# harjapiirilevy.net
KiCad netlist of a schematic drawn in EAGLE
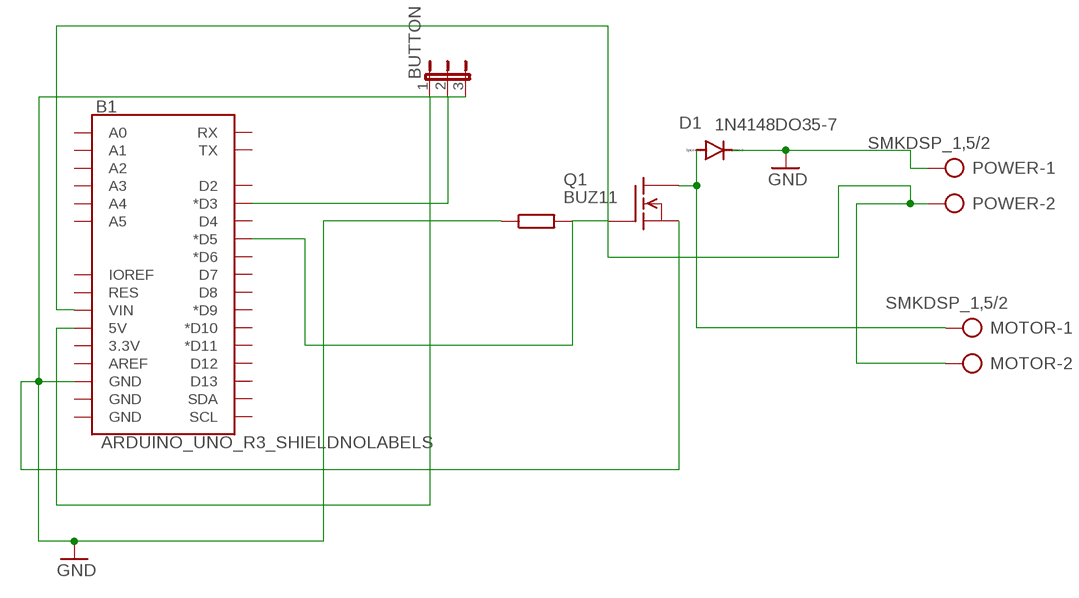
[diagram p0: schematic, sheet 1]

(export (version "E")
  (design (tool "Eeschema 10.0.6"))
  (components
    (comp (ref "B1")
      (value "ARDUINO_UNO_R3_SHIELDNOLABELS")
      (footprint "eagle-import:UNO_R3_SHIELD_NOLABELS")
      (libsource (lib "eagle-import") (part "ARDUINO_UNO_R3_SHIELDNOLABELS"))
    )
    (comp (ref "BUTTON")
      (value "JP2E")
      (footprint "eagle-import:JP2")
      (libsource (lib "eagle-import") (part "JP2E"))
    )
    (comp (ref "D1")
      (value "1N4148DO35-7")
      (footprint "eagle-import:DO35-7")
      (libsource (lib "eagle-import") (part "1N4148DO35-7"))
    )
    (comp (ref "MOTOR")
      (value "SMKDSP_1,5/2")
      (footprint "eagle-import:SMKDSP_1,5_2")
      (fields (field (name "MF") "FARNELL") (field (name "MPN") "1733570"))
      (libsource (lib "eagle-import") (part "SMKDSP_1,5/2"))
    )
    (comp (ref "POWER")
      (value "SMKDSP_1,5/2")
      (footprint "eagle-import:SMKDSP_1,5_2")
      (fields (field (name "MF") "FARNELL") (field (name "MPN") "1733570"))
      (libsource (lib "eagle-import") (part "SMKDSP_1,5/2"))
    )
    (comp (ref "Q1")
      (value "BUZ11")
      (footprint "eagle-import:TO220")
      (libsource (lib "eagle-import") (part "BUZ11"))
    )
  )
  (nets
    (net (code "1") (name "GND") (class "Default")
      (node (ref "B1") (pin "GND@2") (pinfunction "GND_GND@2") (pintype "bidirectional"))
      (node (ref "BUTTON") (pin "3") (pinfunction "3_3") (pintype "passive"))
      (node (ref "D1") (pin "C") (pinfunction "C_C") (pintype "passive"))
      (node (ref "POWER") (pin "1") (pinfunction "KL_1") (pintype "passive"))
      (node (ref "Q1") (pin "3") (pinfunction "S_3") (pintype "passive"))
    )
    (net (code "2") (name "Net-(B1-*D3)") (class "Default")
      (node (ref "B1") (pin "D3") (pinfunction "*D3_D3") (pintype "bidirectional"))
      (node (ref "BUTTON") (pin "2") (pinfunction "2_2") (pintype "passive"))
    )
    (net (code "3") (name "Net-(B1-*D5)") (class "Default")
      (node (ref "B1") (pin "D5") (pinfunction "*D5_D5") (pintype "bidirectional"))
      (node (ref "Q1") (pin "1") (pinfunction "G_1") (pintype "passive"))
    )
    (net (code "4") (name "Net-(B1-Pad5V)") (class "Default")
      (node (ref "B1") (pin "5V") (pinfunction "5V_5V") (pintype "bidirectional"))
      (node (ref "BUTTON") (pin "1") (pinfunction "1_1") (pintype "passive"))
    )
    (net (code "5") (name "Net-(MOTORA-KL)") (class "Default")
      (node (ref "D1") (pin "A") (pinfunction "A_A") (pintype "passive"))
      (node (ref "MOTOR") (pin "1") (pinfunction "KL_1") (pintype "passive"))
      (node (ref "Q1") (pin "2") (pinfunction "D_2") (pintype "passive"))
    )
    (net (code "6") (name "Net-(MOTORB-KL)") (class "Default")
      (node (ref "B1") (pin "VIN") (pinfunction "VIN_VIN") (pintype "bidirectional"))
      (node (ref "MOTOR") (pin "2") (pinfunction "KL_2") (pintype "passive"))
      (node (ref "POWER") (pin "2") (pinfunction "KL_2") (pintype "passive"))
    )
    (net (code "7") (name "unconnected-(B1-*D6-PadD6)") (class "Default")
      (node (ref "B1") (pin "D6") (pinfunction "*D6_D6") (pintype "bidirectional"))
    )
    (net (code "8") (name "unconnected-(B1-*D9-PadD9)") (class "Default")
      (node (ref "B1") (pin "D9") (pinfunction "*D9_D9") (pintype "bidirectional"))
    )
    (net (code "9") (name "unconnected-(B1-*D10-PadD10)") (class "Default")
      (node (ref "B1") (pin "D10") (pinfunction "*D10_D10") (pintype "bidirectional"))
    )
    (net (code "10") (name "unconnected-(B1-*D11-PadD11)") (class "Default")
      (node (ref "B1") (pin "D11") (pinfunction "*D11_D11") (pintype "bidirectional"))
    )
    (net (code "11") (name "unconnected-(B1-GND-PadGND@0)") (class "Default")
      (node (ref "B1") (pin "GND@0") (pinfunction "GND_GND@0") (pintype "bidirectional"))
    )
    (net (code "12") (name "unconnected-(B1-GND-PadGND@1)") (class "Default")
      (node (ref "B1") (pin "GND@1") (pinfunction "GND_GND@1") (pintype "bidirectional"))
    )
    (net (code "13") (name "unconnected-(B1-Pad3.3V)") (class "Default")
      (node (ref "B1") (pin "3.3V") (pinfunction "3.3V_3.3V") (pintype "bidirectional"))
    )
    (net (code "14") (name "unconnected-(B1-PadA0)") (class "Default")
      (node (ref "B1") (pin "A0") (pinfunction "A0_A0") (pintype "bidirectional"))
    )
    (net (code "15") (name "unconnected-(B1-PadA1)") (class "Default")
      (node (ref "B1") (pin "A1") (pinfunction "A1_A1") (pintype "bidirectional"))
    )
    (net (code "16") (name "unconnected-(B1-PadA2)") (class "Default")
      (node (ref "B1") (pin "A2") (pinfunction "A2_A2") (pintype "bidirectional"))
    )
    (net (code "17") (name "unconnected-(B1-PadA3)") (class "Default")
      (node (ref "B1") (pin "A3") (pinfunction "A3_A3") (pintype "bidirectional"))
    )
    (net (code "18") (name "unconnected-(B1-PadA4)") (class "Default")
      (node (ref "B1") (pin "A4") (pinfunction "A4_A4") (pintype "bidirectional"))
    )
    (net (code "19") (name "unconnected-(B1-PadA5)") (class "Default")
      (node (ref "B1") (pin "A5") (pinfunction "A5_A5") (pintype "bidirectional"))
    )
    (net (code "20") (name "unconnected-(B1-PadAREF)") (class "Default")
      (node (ref "B1") (pin "AREF") (pinfunction "AREF_AREF") (pintype "bidirectional"))
    )
    (net (code "21") (name "unconnected-(B1-PadD2)") (class "Default")
      (node (ref "B1") (pin "D2") (pinfunction "D2_D2") (pintype "bidirectional"))
    )
    (net (code "22") (name "unconnected-(B1-PadD4)") (class "Default")
      (node (ref "B1") (pin "D4") (pinfunction "D4_D4") (pintype "bidirectional"))
    )
    (net (code "23") (name "unconnected-(B1-PadD7)") (class "Default")
      (node (ref "B1") (pin "D7") (pinfunction "D7_D7") (pintype "bidirectional"))
    )
    (net (code "24") (name "unconnected-(B1-PadD8)") (class "Default")
      (node (ref "B1") (pin "D8") (pinfunction "D8_D8") (pintype "bidirectional"))
    )
    (net (code "25") (name "unconnected-(B1-PadD12)") (class "Default")
      (node (ref "B1") (pin "D12") (pinfunction "D12_D12") (pintype "bidirectional"))
    )
    (net (code "26") (name "unconnected-(B1-PadD13)") (class "Default")
      (node (ref "B1") (pin "D13") (pinfunction "D13_D13") (pintype "bidirectional"))
    )
    (net (code "27") (name "unconnected-(B1-PadIOREF)") (class "Default")
      (node (ref "B1") (pin "IOREF") (pinfunction "IOREF_IOREF") (pintype "bidirectional"))
    )
    (net (code "28") (name "unconnected-(B1-PadRES)") (class "Default")
      (node (ref "B1") (pin "RES") (pinfunction "RES_RES") (pintype "bidirectional"))
    )
    (net (code "29") (name "unconnected-(B1-PadRX)") (class "Default")
      (node (ref "B1") (pin "RX") (pinfunction "RX_RX") (pintype "bidirectional"))
    )
    (net (code "30") (name "unconnected-(B1-PadSCL)") (class "Default")
      (node (ref "B1") (pin "SCL") (pinfunction "SCL_SCL") (pintype "bidirectional"))
    )
    (net (code "31") (name "unconnected-(B1-PadSDA)") (class "Default")
      (node (ref "B1") (pin "SDA") (pinfunction "SDA_SDA") (pintype "bidirectional"))
    )
    (net (code "32") (name "unconnected-(B1-PadTX)") (class "Default")
      (node (ref "B1") (pin "TX") (pinfunction "TX_TX") (pintype "bidirectional"))
    )
  )
)
